# Audio.net
KiCad netlist of a schematic drawn in Altium Designer
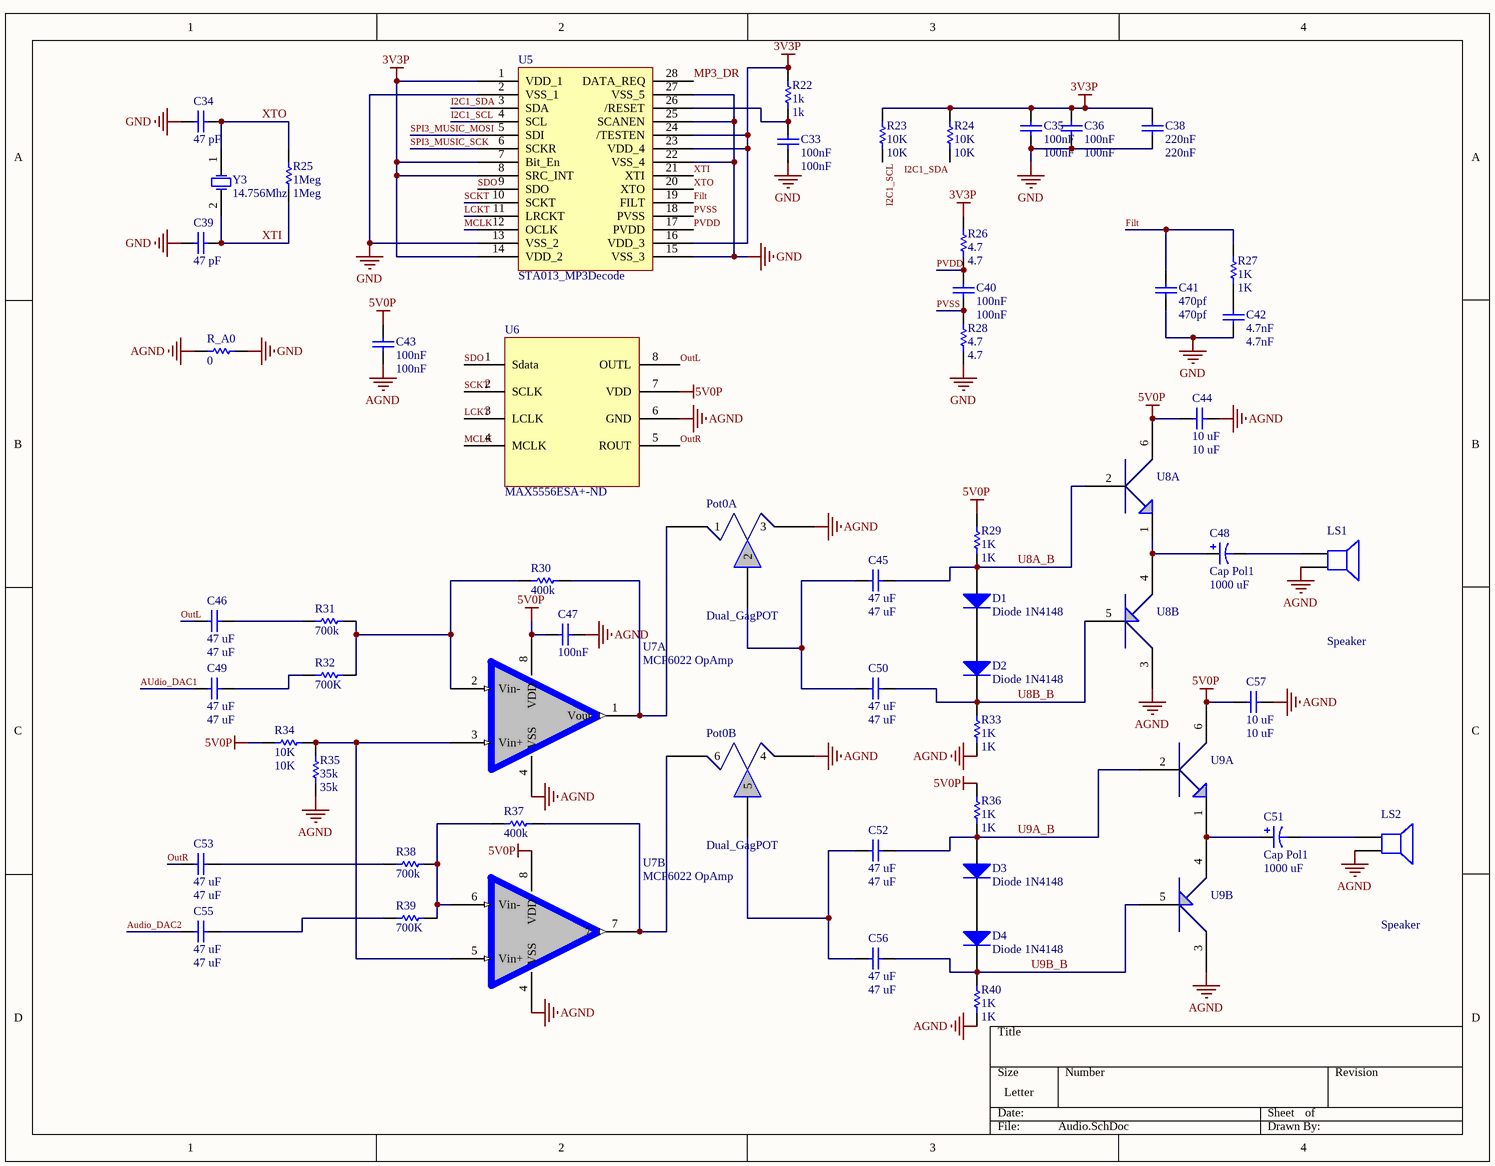
[diagram p0: Audio.SchDoc]

(export (version "E")
  (design (tool "Eeschema 10.0.6"))
  (components
    (comp (ref "C33")
      (value "100nF")
      (footprint "C0805")
      (description "Capacitor")
      (fields (field (name "ALTIUM_VALUE") "100nF") (field (name "PUBLISHER") "Altium Limited"))
      (libsource (lib "Miscellaneous Devices") (part "Cap"))
    )
    (comp (ref "C34")
      (value "47 pF")
      (footprint "C0805")
      (description "Capacitor")
      (fields (field (name "PUBLISHER") "Altium Limited"))
      (libsource (lib "Miscellaneous Devices") (part "Cap"))
    )
    (comp (ref "C35")
      (value "100nF")
      (footprint "C0805")
      (description "Capacitor")
      (fields (field (name "ALTIUM_VALUE") "100nF") (field (name "PUBLISHER") "Altium Limited"))
      (libsource (lib "Miscellaneous Devices") (part "Cap"))
    )
    (comp (ref "C36")
      (value "100nF")
      (footprint "C0805")
      (description "Capacitor")
      (fields (field (name "ALTIUM_VALUE") "100nF") (field (name "PUBLISHER") "Altium Limited"))
      (libsource (lib "Miscellaneous Devices") (part "Cap"))
    )
    (comp (ref "C38")
      (value "220nF")
      (footprint "C0805")
      (description "Capacitor")
      (fields (field (name "ALTIUM_VALUE") "220nF") (field (name "PUBLISHER") "Altium Limited"))
      (libsource (lib "Miscellaneous Devices") (part "Cap"))
    )
    (comp (ref "C39")
      (value "47 pF")
      (footprint "C0805")
      (description "Capacitor")
      (fields (field (name "PUBLISHER") "Altium Limited"))
      (libsource (lib "Miscellaneous Devices") (part "Cap"))
    )
    (comp (ref "C40")
      (value "100nF")
      (footprint "C0805")
      (description "Capacitor")
      (fields (field (name "ALTIUM_VALUE") "100nF") (field (name "PUBLISHER") "Altium Limited"))
      (libsource (lib "Miscellaneous Devices") (part "Cap"))
    )
    (comp (ref "C41")
      (value "470pf")
      (footprint "C0805")
      (description "Capacitor")
      (fields (field (name "ALTIUM_VALUE") "470pf") (field (name "PUBLISHER") "Altium Limited"))
      (libsource (lib "Miscellaneous Devices") (part "Cap"))
    )
    (comp (ref "C42")
      (value "4.7nF")
      (footprint "C0805")
      (description "Capacitor")
      (fields (field (name "ALTIUM_VALUE") "4.7nF") (field (name "PUBLISHER") "Altium Limited"))
      (libsource (lib "Miscellaneous Devices") (part "Cap"))
    )
    (comp (ref "C43")
      (value "100nF")
      (footprint "C0805")
      (description "Capacitor")
      (fields (field (name "ALTIUM_VALUE") "100nF") (field (name "PUBLISHER") "Altium Limited"))
      (libsource (lib "Miscellaneous Devices") (part "Cap"))
    )
    (comp (ref "C44")
      (value "10 uF")
      (footprint "C0805")
      (description "Capacitor")
      (fields (field (name "ALTIUM_VALUE") "10 uF") (field (name "PUBLISHER") "Altium Limited"))
      (libsource (lib "Miscellaneous Devices") (part "Cap"))
    )
    (comp (ref "C45")
      (value "47 uF")
      (footprint "C0805")
      (description "Capacitor")
      (fields (field (name "ALTIUM_VALUE") "47 uF") (field (name "PUBLISHER") "Altium Limited"))
      (libsource (lib "Miscellaneous Devices") (part "Cap"))
    )
    (comp (ref "C46")
      (value "47 uF")
      (footprint "C0805")
      (description "Capacitor")
      (fields (field (name "ALTIUM_VALUE") "47 uF") (field (name "PUBLISHER") "Altium Limited"))
      (libsource (lib "Miscellaneous Devices") (part "Cap"))
    )
    (comp (ref "C47")
      (value "100nF")
      (footprint "C0805")
      (description "Capacitor")
      (fields (field (name "PUBLISHER") "Altium Limited"))
      (libsource (lib "Miscellaneous Devices") (part "Cap"))
    )
    (comp (ref "C48")
      (value "Cap Pol1")
      (footprint "C2917")
      (description "Polarized Capacitor (Radial)")
      (fields (field (name "ALTIUM_VALUE") "1000 uF") (field (name "PUBLISHER") "Altium Limited"))
      (libsource (lib "Miscellaneous Devices") (part "Cap Pol1"))
    )
    (comp (ref "C49")
      (value "47 uF")
      (footprint "C0805")
      (description "Capacitor")
      (fields (field (name "ALTIUM_VALUE") "47 uF") (field (name "PUBLISHER") "Altium Limited"))
      (libsource (lib "Miscellaneous Devices") (part "Cap"))
    )
    (comp (ref "C50")
      (value "47 uF")
      (footprint "C0805")
      (description "Capacitor")
      (fields (field (name "ALTIUM_VALUE") "47 uF") (field (name "PUBLISHER") "Altium Limited"))
      (libsource (lib "Miscellaneous Devices") (part "Cap"))
    )
    (comp (ref "C51")
      (value "Cap Pol1")
      (footprint "C2917")
      (description "Polarized Capacitor (Radial)")
      (fields (field (name "ALTIUM_VALUE") "1000 uF") (field (name "PUBLISHER") "Altium Limited"))
      (libsource (lib "Miscellaneous Devices") (part "Cap Pol1"))
    )
    (comp (ref "C52")
      (value "47 uF")
      (footprint "C0805")
      (description "Capacitor")
      (fields (field (name "ALTIUM_VALUE") "47 uF") (field (name "PUBLISHER") "Altium Limited"))
      (libsource (lib "Miscellaneous Devices") (part "Cap"))
    )
    (comp (ref "C53")
      (value "47 uF")
      (footprint "C0805")
      (description "Capacitor")
      (fields (field (name "ALTIUM_VALUE") "47 uF") (field (name "PUBLISHER") "Altium Limited"))
      (libsource (lib "Miscellaneous Devices") (part "Cap"))
    )
    (comp (ref "C55")
      (value "47 uF")
      (footprint "C0805")
      (description "Capacitor")
      (fields (field (name "ALTIUM_VALUE") "47 uF") (field (name "PUBLISHER") "Altium Limited"))
      (libsource (lib "Miscellaneous Devices") (part "Cap"))
    )
    (comp (ref "C56")
      (value "47 uF")
      (footprint "C0805")
      (description "Capacitor")
      (fields (field (name "ALTIUM_VALUE") "47 uF") (field (name "PUBLISHER") "Altium Limited"))
      (libsource (lib "Miscellaneous Devices") (part "Cap"))
    )
    (comp (ref "C57")
      (value "10 uF")
      (footprint "C0805")
      (description "Capacitor")
      (fields (field (name "ALTIUM_VALUE") "10 uF") (field (name "PUBLISHER") "Altium Limited"))
      (libsource (lib "Miscellaneous Devices") (part "Cap"))
    )
    (comp (ref "D1")
      (value "Diode 1N4148")
      (footprint "Diode")
      (description "High Conductance Fast Diode")
      (fields (field (name "PUBLISHER") "Altium Limited"))
      (libsource (lib "Miscellaneous Devices") (part "Diode 1N4148"))
    )
    (comp (ref "D2")
      (value "Diode 1N4148")
      (footprint "Diode")
      (description "High Conductance Fast Diode")
      (fields (field (name "PUBLISHER") "Altium Limited"))
      (libsource (lib "Miscellaneous Devices") (part "Diode 1N4148"))
    )
    (comp (ref "D3")
      (value "Diode 1N4148")
      (footprint "Diode")
      (description "High Conductance Fast Diode")
      (fields (field (name "PUBLISHER") "Altium Limited"))
      (libsource (lib "Miscellaneous Devices") (part "Diode 1N4148"))
    )
    (comp (ref "D4")
      (value "Diode 1N4148")
      (footprint "Diode")
      (description "High Conductance Fast Diode")
      (fields (field (name "PUBLISHER") "Altium Limited"))
      (libsource (lib "Miscellaneous Devices") (part "Diode 1N4148"))
    )
    (comp (ref "LS1")
      (value "Speaker")
      (footprint "PIN2")
      (description "Loudspeaker")
      (fields (field (name "PUBLISHER") "Altium Limited"))
      (libsource (lib "Miscellaneous Devices") (part "Speaker"))
    )
    (comp (ref "LS2")
      (value "Speaker")
      (footprint "PIN2")
      (description "Loudspeaker")
      (fields (field (name "PUBLISHER") "Altium Limited"))
      (libsource (lib "Miscellaneous Devices") (part "Speaker"))
    )
    (comp (ref "Pot0")
      (value "Dual_GagPOT")
      (footprint "DGPOT")
      (libsource (lib "GameMan_SchLib") (part "Dual_GagPOT"))
    )
    (comp (ref "R22")
      (value "1k")
      (footprint "6-0805_M")
      (description "Resistor")
      (fields (field (name "ALTIUM_VALUE") "1k") (field (name "PUBLISHER") "Altium Limited"))
      (libsource (lib "Miscellaneous Devices") (part "Res1"))
    )
    (comp (ref "R23")
      (value "10K")
      (footprint "6-0805_M")
      (description "Resistor")
      (fields (field (name "ALTIUM_VALUE") "10K") (field (name "PUBLISHER") "Altium Limited"))
      (libsource (lib "Miscellaneous Devices") (part "Res1"))
    )
    (comp (ref "R24")
      (value "10K")
      (footprint "6-0805_M")
      (description "Resistor")
      (fields (field (name "ALTIUM_VALUE") "10K") (field (name "PUBLISHER") "Altium Limited"))
      (libsource (lib "Miscellaneous Devices") (part "Res1"))
    )
    (comp (ref "R25")
      (value "1Meg")
      (footprint "6-0805_M")
      (description "Resistor")
      (fields (field (name "ALTIUM_VALUE") "1Meg") (field (name "PUBLISHER") "Altium Limited"))
      (libsource (lib "Miscellaneous Devices") (part "Res1"))
    )
    (comp (ref "R26")
      (value "4.7")
      (footprint "6-0805_M")
      (description "Resistor")
      (fields (field (name "ALTIUM_VALUE") "4.7") (field (name "PUBLISHER") "Altium Limited"))
      (libsource (lib "Miscellaneous Devices") (part "Res1"))
    )
    (comp (ref "R27")
      (value "1K")
      (footprint "6-0805_M")
      (description "Resistor")
      (fields (field (name "ALTIUM_VALUE") "1K") (field (name "PUBLISHER") "Altium Limited"))
      (libsource (lib "Miscellaneous Devices") (part "Res1"))
    )
    (comp (ref "R28")
      (value "4.7")
      (footprint "6-0805_M")
      (description "Resistor")
      (fields (field (name "ALTIUM_VALUE") "4.7") (field (name "PUBLISHER") "Altium Limited"))
      (libsource (lib "Miscellaneous Devices") (part "Res1"))
    )
    (comp (ref "R29")
      (value "1K")
      (footprint "6-0805_M")
      (description "Resistor")
      (fields (field (name "ALTIUM_VALUE") "1K") (field (name "PUBLISHER") "Altium Limited"))
      (libsource (lib "Miscellaneous Devices") (part "Res1"))
    )
    (comp (ref "R30")
      (value "400k")
      (footprint "6-0805_M")
      (description "Resistor")
      (fields (field (name "PUBLISHER") "Altium Limited"))
      (libsource (lib "Miscellaneous Devices") (part "Res1"))
    )
    (comp (ref "R31")
      (value "700k")
      (footprint "6-0805_M")
      (description "Resistor")
      (fields (field (name "PUBLISHER") "Altium Limited"))
      (libsource (lib "Miscellaneous Devices") (part "Res1"))
    )
    (comp (ref "R32")
      (value "700K")
      (footprint "6-0805_M")
      (description "Resistor")
      (fields (field (name "PUBLISHER") "Altium Limited"))
      (libsource (lib "Miscellaneous Devices") (part "Res1"))
    )
    (comp (ref "R33")
      (value "1K")
      (footprint "6-0805_M")
      (description "Resistor")
      (fields (field (name "ALTIUM_VALUE") "1K") (field (name "PUBLISHER") "Altium Limited"))
      (libsource (lib "Miscellaneous Devices") (part "Res1"))
    )
    (comp (ref "R34")
      (value "10K")
      (footprint "6-0805_M")
      (description "Resistor")
      (fields (field (name "ALTIUM_VALUE") "10K") (field (name "PUBLISHER") "Altium Limited"))
      (libsource (lib "Miscellaneous Devices") (part "Res1"))
    )
    (comp (ref "R35")
      (value "35k")
      (footprint "6-0805_M")
      (description "Resistor")
      (fields (field (name "ALTIUM_VALUE") "35k") (field (name "PUBLISHER") "Altium Limited"))
      (libsource (lib "Miscellaneous Devices") (part "Res1"))
    )
    (comp (ref "R36")
      (value "1K")
      (footprint "6-0805_M")
      (description "Resistor")
      (fields (field (name "ALTIUM_VALUE") "1K") (field (name "PUBLISHER") "Altium Limited"))
      (libsource (lib "Miscellaneous Devices") (part "Res1"))
    )
    (comp (ref "R37")
      (value "400k")
      (footprint "6-0805_M")
      (description "Resistor")
      (fields (field (name "PUBLISHER") "Altium Limited"))
      (libsource (lib "Miscellaneous Devices") (part "Res1"))
    )
    (comp (ref "R38")
      (value "700k")
      (footprint "6-0805_M")
      (description "Resistor")
      (fields (field (name "PUBLISHER") "Altium Limited"))
      (libsource (lib "Miscellaneous Devices") (part "Res1"))
    )
    (comp (ref "R39")
      (value "700K")
      (footprint "6-0805_M")
      (description "Resistor")
      (fields (field (name "PUBLISHER") "Altium Limited"))
      (libsource (lib "Miscellaneous Devices") (part "Res1"))
    )
    (comp (ref "R40")
      (value "1K")
      (footprint "6-0805_M")
      (description "Resistor")
      (fields (field (name "ALTIUM_VALUE") "1K") (field (name "PUBLISHER") "Altium Limited"))
      (libsource (lib "Miscellaneous Devices") (part "Res1"))
    )
    (comp (ref "R_A0")
      (value "0")
      (footprint "6-0805_M")
      (description "Resistor")
      (fields (field (name "PUBLISHER") "Altium Limited"))
      (libsource (lib "Miscellaneous Devices") (part "Res1"))
    )
    (comp (ref "U5")
      (value "STA013_MP3Decode")
      (footprint "SOP28")
      (libsource (lib "Parts") (part "STA013_MP3Decode"))
    )
    (comp (ref "U6")
      (value "MAX5556ESA+-ND")
      (footprint "SOIC8_DAC")
      (libsource (lib "Parts") (part "MAX5556ESA+-ND"))
    )
    (comp (ref "U7")
      (value "MCP6022 OpAmp")
      (footprint "SOP8_Opamp")
      (libsource (lib "GameMan") (part "MCP6022 OpAmp"))
    )
    (comp (ref "U8") (value "BJT") (footprint "BJT_SOT6") (libsource (lib "GameMan") (part "BJT")))
    (comp (ref "U9") (value "BJT") (footprint "BJT_SOT6") (libsource (lib "GameMan") (part "BJT")))
    (comp (ref "Y3")
      (value "14.756Mhz")
      (footprint "HC-49U")
      (description "Crystal Oscillator")
      (fields (field (name "PUBLISHER") "Altium Limited"))
      (libsource (lib "Miscellaneous Devices") (part "XTAL"))
    )
  )
  (nets
    (net (code "1") (name "/AUdio_DAC1") (class "Default")
      (node (ref "C49") (pin "1") (pinfunction "1_1") (pintype "passive"))
    )
    (net (code "2") (name "/Audio_DAC2") (class "Default")
      (node (ref "C55") (pin "1") (pinfunction "1_1") (pintype "passive"))
    )
    (net (code "3") (name "/Filt") (class "Default")
      (node (ref "C41") (pin "2") (pinfunction "2_2") (pintype "passive"))
      (node (ref "R27") (pin "1") (pinfunction "1_1") (pintype "passive"))
      (node (ref "U5") (pin "19") (pinfunction "FILT_19") (pintype "passive"))
    )
    (net (code "4") (name "/I2C1_SCL") (class "Default")
      (node (ref "R23") (pin "1") (pinfunction "1_1") (pintype "passive"))
      (node (ref "U5") (pin "4") (pinfunction "SCL_4") (pintype "passive"))
    )
    (net (code "5") (name "/I2C1_SDA") (class "Default")
      (node (ref "R24") (pin "1") (pinfunction "1_1") (pintype "passive"))
      (node (ref "U5") (pin "3") (pinfunction "SDA_3") (pintype "passive"))
    )
    (net (code "6") (name "/LCKT") (class "Default")
      (node (ref "U5") (pin "11") (pinfunction "LRCKT_11") (pintype "passive"))
      (node (ref "U6") (pin "3") (pinfunction "LCLK_3") (pintype "passive"))
    )
    (net (code "7") (name "/MCLK") (class "Default")
      (node (ref "U5") (pin "12") (pinfunction "OCLK_12") (pintype "passive"))
      (node (ref "U6") (pin "4") (pinfunction "MCLK_4") (pintype "passive"))
    )
    (net (code "8") (name "/MP3_DR") (class "Default")
      (node (ref "U5") (pin "28") (pinfunction "DATA_REQ_28") (pintype "passive"))
    )
    (net (code "9") (name "/OutL") (class "Default")
      (node (ref "C46") (pin "1") (pinfunction "1_1") (pintype "passive"))
      (node (ref "U6") (pin "8") (pinfunction "OUTL_8") (pintype "passive"))
    )
    (net (code "10") (name "/OutR") (class "Default")
      (node (ref "C53") (pin "1") (pinfunction "1_1") (pintype "passive"))
      (node (ref "U6") (pin "5") (pinfunction "ROUT_5") (pintype "passive"))
    )
    (net (code "11") (name "/PVDD") (class "Default")
      (node (ref "C40") (pin "2") (pinfunction "2_2") (pintype "passive"))
      (node (ref "R26") (pin "2") (pinfunction "2_2") (pintype "passive"))
      (node (ref "U5") (pin "17") (pinfunction "PVDD_17") (pintype "passive"))
    )
    (net (code "12") (name "/PVSS") (class "Default")
      (node (ref "C40") (pin "1") (pinfunction "1_1") (pintype "passive"))
      (node (ref "R28") (pin "1") (pinfunction "1_1") (pintype "passive"))
      (node (ref "U5") (pin "18") (pinfunction "PVSS_18") (pintype "passive"))
    )
    (net (code "13") (name "/SCKT") (class "Default")
      (node (ref "U5") (pin "10") (pinfunction "SCKT_10") (pintype "passive"))
      (node (ref "U6") (pin "2") (pinfunction "SCLK_2") (pintype "passive"))
    )
    (net (code "14") (name "/SDO") (class "Default")
      (node (ref "U5") (pin "9") (pinfunction "SDO_9") (pintype "passive"))
      (node (ref "U6") (pin "1") (pinfunction "Sdata_1") (pintype "passive"))
    )
    (net (code "15") (name "/SPI3_MUSIC_MOSI") (class "Default")
      (node (ref "U5") (pin "5") (pinfunction "SDI_5") (pintype "passive"))
    )
    (net (code "16") (name "/SPI3_MUSIC_SCK") (class "Default")
      (node (ref "U5") (pin "6") (pinfunction "SCKR_6") (pintype "passive"))
    )
    (net (code "17") (name "/U8A_B") (class "Default")
      (node (ref "C45") (pin "2") (pinfunction "2_2") (pintype "passive"))
      (node (ref "D1") (pin "A") (pinfunction "A_A") (pintype "passive"))
      (node (ref "R29") (pin "2") (pinfunction "2_2") (pintype "passive"))
      (node (ref "U8") (pin "2") (pinfunction "Base_2") (pintype "power_in"))
    )
    (net (code "18") (name "/U8B_B") (class "Default")
      (node (ref "C50") (pin "2") (pinfunction "2_2") (pintype "passive"))
      (node (ref "D2") (pin "K") (pinfunction "K_K") (pintype "passive"))
      (node (ref "R33") (pin "1") (pinfunction "1_1") (pintype "passive"))
      (node (ref "U8") (pin "5") (pinfunction "Base_5") (pintype "power_in"))
    )
    (net (code "19") (name "/U9A_B") (class "Default")
      (node (ref "C52") (pin "2") (pinfunction "2_2") (pintype "passive"))
      (node (ref "D3") (pin "A") (pinfunction "A_A") (pintype "passive"))
      (node (ref "R36") (pin "2") (pinfunction "2_2") (pintype "passive"))
      (node (ref "U9") (pin "2") (pinfunction "Base_2") (pintype "power_in"))
    )
    (net (code "20") (name "/U9B_B") (class "Default")
      (node (ref "C56") (pin "2") (pinfunction "2_2") (pintype "passive"))
      (node (ref "D4") (pin "K") (pinfunction "K_K") (pintype "passive"))
      (node (ref "R40") (pin "1") (pinfunction "1_1") (pintype "passive"))
      (node (ref "U9") (pin "5") (pinfunction "Base_5") (pintype "power_in"))
    )
    (net (code "21") (name "/XTI") (class "Default")
      (node (ref "C39") (pin "2") (pinfunction "2_2") (pintype "passive"))
      (node (ref "R25") (pin "1") (pinfunction "1_1") (pintype "passive"))
      (node (ref "U5") (pin "21") (pinfunction "XTI_21") (pintype "passive"))
      (node (ref "Y3") (pin "2") (pinfunction "OSC2_2") (pintype "passive"))
    )
    (net (code "22") (name "/XTO") (class "Default")
      (node (ref "C34") (pin "2") (pinfunction "2_2") (pintype "passive"))
      (node (ref "R25") (pin "2") (pinfunction "2_2") (pintype "passive"))
      (node (ref "U5") (pin "20") (pinfunction "XTO_20") (pintype "passive"))
      (node (ref "Y3") (pin "1") (pinfunction "OSC1_1") (pintype "passive"))
    )
    (net (code "23") (name "3V3P") (class "Default")
      (node (ref "C35") (pin "2") (pinfunction "2_2") (pintype "passive"))
      (node (ref "C36") (pin "2") (pinfunction "2_2") (pintype "passive"))
      (node (ref "C38") (pin "2") (pinfunction "2_2") (pintype "passive"))
      (node (ref "R22") (pin "2") (pinfunction "2_2") (pintype "passive"))
      (node (ref "R23") (pin "2") (pinfunction "2_2") (pintype "passive"))
      (node (ref "R24") (pin "2") (pinfunction "2_2") (pintype "passive"))
      (node (ref "R26") (pin "1") (pinfunction "1_1") (pintype "passive"))
      (node (ref "U5") (pin "1") (pinfunction "VDD_1_1") (pintype "passive"))
      (node (ref "U5") (pin "14") (pinfunction "VDD_2_14") (pintype "passive"))
      (node (ref "U5") (pin "16") (pinfunction "VDD_3_16") (pintype "passive"))
      (node (ref "U5") (pin "23") (pinfunction "VDD_4_23") (pintype "passive"))
      (node (ref "U5") (pin "24") (pinfunction "/TESTEN_24") (pintype "passive"))
      (node (ref "U5") (pin "7") (pinfunction "Bit_En_7") (pintype "passive"))
      (node (ref "U5") (pin "8") (pinfunction "SRC_INT_8") (pintype "passive"))
    )
    (net (code "24") (name "5V0P") (class "Default")
      (node (ref "C43") (pin "2") (pinfunction "2_2") (pintype "passive"))
      (node (ref "C44") (pin "2") (pinfunction "2_2") (pintype "passive"))
      (node (ref "C47") (pin "1") (pinfunction "1_1") (pintype "passive"))
      (node (ref "C57") (pin "2") (pinfunction "2_2") (pintype "passive"))
      (node (ref "R29") (pin "1") (pinfunction "1_1") (pintype "passive"))
      (node (ref "R34") (pin "1") (pinfunction "1_1") (pintype "passive"))
      (node (ref "R36") (pin "1") (pinfunction "1_1") (pintype "passive"))
      (node (ref "U6") (pin "7") (pinfunction "VDD_7") (pintype "passive"))
      (node (ref "U7") (pin "8") (pinfunction "VDD_8") (pintype "power_in"))
      (node (ref "U8") (pin "6") (pinfunction "Collector_6") (pintype "power_in"))
      (node (ref "U9") (pin "6") (pinfunction "Collector_6") (pintype "power_in"))
    )
    (net (code "25") (name "AGND") (class "Default")
      (node (ref "C43") (pin "1") (pinfunction "1_1") (pintype "passive"))
      (node (ref "C44") (pin "1") (pinfunction "1_1") (pintype "passive"))
      (node (ref "C47") (pin "2") (pinfunction "2_2") (pintype "passive"))
      (node (ref "C57") (pin "1") (pinfunction "1_1") (pintype "passive"))
      (node (ref "LS1") (pin "2") (pinfunction "2_2") (pintype "passive"))
      (node (ref "LS2") (pin "2") (pinfunction "2_2") (pintype "passive"))
      (node (ref "Pot0") (pin "3") (pinfunction "3_3") (pintype "passive"))
      (node (ref "Pot0") (pin "4") (pinfunction "4_4") (pintype "passive"))
      (node (ref "R33") (pin "2") (pinfunction "2_2") (pintype "passive"))
      (node (ref "R35") (pin "1") (pinfunction "1_1") (pintype "passive"))
      (node (ref "R40") (pin "2") (pinfunction "2_2") (pintype "passive"))
      (node (ref "R_A0") (pin "1") (pinfunction "1_1") (pintype "passive"))
      (node (ref "U6") (pin "6") (pinfunction "GND_6") (pintype "passive"))
      (node (ref "U7") (pin "4") (pinfunction "VSS_4") (pintype "power_in"))
      (node (ref "U8") (pin "3") (pinfunction "Collector_3") (pintype "power_in"))
      (node (ref "U9") (pin "3") (pinfunction "Collector_3") (pintype "power_in"))
    )
    (net (code "26") (name "GND") (class "Default")
      (node (ref "C33") (pin "2") (pinfunction "2_2") (pintype "passive"))
      (node (ref "C34") (pin "1") (pinfunction "1_1") (pintype "passive"))
      (node (ref "C35") (pin "1") (pinfunction "1_1") (pintype "passive"))
      (node (ref "C36") (pin "1") (pinfunction "1_1") (pintype "passive"))
      (node (ref "C38") (pin "1") (pinfunction "1_1") (pintype "passive"))
      (node (ref "C39") (pin "1") (pinfunction "1_1") (pintype "passive"))
      (node (ref "C41") (pin "1") (pinfunction "1_1") (pintype "passive"))
      (node (ref "C42") (pin "1") (pinfunction "1_1") (pintype "passive"))
      (node (ref "R28") (pin "2") (pinfunction "2_2") (pintype "passive"))
      (node (ref "R_A0") (pin "2") (pinfunction "2_2") (pintype "passive"))
      (node (ref "U5") (pin "13") (pinfunction "VSS_2_13") (pintype "passive"))
      (node (ref "U5") (pin "15") (pinfunction "VSS_3_15") (pintype "passive"))
      (node (ref "U5") (pin "2") (pinfunction "VSS_1_2") (pintype "passive"))
      (node (ref "U5") (pin "22") (pinfunction "VSS_4_22") (pintype "passive"))
      (node (ref "U5") (pin "25") (pinfunction "SCANEN_25") (pintype "passive"))
      (node (ref "U5") (pin "27") (pinfunction "VSS_5_27") (pintype "passive"))
    )
    (net (code "27") (name "Net-(C42-Pad2)") (class "Default")
      (node (ref "C42") (pin "2") (pinfunction "2_2") (pintype "passive"))
      (node (ref "R27") (pin "2") (pinfunction "2_2") (pintype "passive"))
    )
    (net (code "28") (name "Net-(C45-Pad1)") (class "Default")
      (node (ref "C45") (pin "1") (pinfunction "1_1") (pintype "passive"))
      (node (ref "C50") (pin "1") (pinfunction "1_1") (pintype "passive"))
      (node (ref "Pot0") (pin "2") (pinfunction "2_2") (pintype "passive"))
    )
    (net (code "29") (name "Net-(C46-Pad2)") (class "Default")
      (node (ref "C46") (pin "2") (pinfunction "2_2") (pintype "passive"))
      (node (ref "R31") (pin "1") (pinfunction "1_1") (pintype "passive"))
    )
    (net (code "30") (name "Net-(C48-Pad2)") (class "Default")
      (node (ref "C48") (pin "2") (pinfunction "2_2") (pintype "passive"))
      (node (ref "LS1") (pin "1") (pinfunction "1_1") (pintype "passive"))
    )
    (net (code "31") (name "Net-(C49-Pad2)") (class "Default")
      (node (ref "C49") (pin "2") (pinfunction "2_2") (pintype "passive"))
      (node (ref "R32") (pin "1") (pinfunction "1_1") (pintype "passive"))
    )
    (net (code "32") (name "Net-(C51-Pad2)") (class "Default")
      (node (ref "C51") (pin "2") (pinfunction "2_2") (pintype "passive"))
      (node (ref "LS2") (pin "1") (pinfunction "1_1") (pintype "passive"))
    )
    (net (code "33") (name "Net-(C52-Pad1)") (class "Default")
      (node (ref "C52") (pin "1") (pinfunction "1_1") (pintype "passive"))
      (node (ref "C56") (pin "1") (pinfunction "1_1") (pintype "passive"))
      (node (ref "Pot0") (pin "5") (pinfunction "5_5") (pintype "passive"))
    )
    (net (code "34") (name "Net-(C53-Pad2)") (class "Default")
      (node (ref "C53") (pin "2") (pinfunction "2_2") (pintype "passive"))
      (node (ref "R38") (pin "1") (pinfunction "1_1") (pintype "passive"))
    )
    (net (code "35") (name "Net-(C55-Pad2)") (class "Default")
      (node (ref "C55") (pin "2") (pinfunction "2_2") (pintype "passive"))
      (node (ref "R39") (pin "1") (pinfunction "1_1") (pintype "passive"))
    )
    (net (code "36") (name "Net-(D1-PadK)") (class "Default")
      (node (ref "D1") (pin "K") (pinfunction "K_K") (pintype "passive"))
      (node (ref "D2") (pin "A") (pinfunction "A_A") (pintype "passive"))
    )
    (net (code "37") (name "Net-(D3-PadK)") (class "Default")
      (node (ref "D3") (pin "K") (pinfunction "K_K") (pintype "passive"))
      (node (ref "D4") (pin "A") (pinfunction "A_A") (pintype "passive"))
    )
    (net (code "38") (name "Net-(Pot0-Pad6)") (class "Default")
      (node (ref "Pot0") (pin "6") (pinfunction "6_6") (pintype "passive"))
      (node (ref "R37") (pin "2") (pinfunction "2_2") (pintype "passive"))
      (node (ref "U7") (pin "7") (pinfunction "7_7") (pintype "output"))
    )
    (net (code "39") (name "Net-(U5-{slash}RESET)") (class "Default")
      (node (ref "C33") (pin "1") (pinfunction "1_1") (pintype "passive"))
      (node (ref "R22") (pin "1") (pinfunction "1_1") (pintype "passive"))
      (node (ref "U5") (pin "26") (pinfunction "/RESET_26") (pintype "passive"))
    )
    (net (code "40") (name "Net-(U7A-Vin+)") (class "Default")
      (node (ref "R34") (pin "2") (pinfunction "2_2") (pintype "passive"))
      (node (ref "R35") (pin "2") (pinfunction "2_2") (pintype "passive"))
      (node (ref "U7") (pin "3") (pinfunction "Vin+_3") (pintype "input"))
      (node (ref "U7") (pin "5") (pinfunction "Vin+_5") (pintype "input"))
    )
    (net (code "41") (name "Net-(U7A-Vin-)") (class "Default")
      (node (ref "R30") (pin "1") (pinfunction "1_1") (pintype "passive"))
      (node (ref "R31") (pin "2") (pinfunction "2_2") (pintype "passive"))
      (node (ref "R32") (pin "2") (pinfunction "2_2") (pintype "passive"))
      (node (ref "U7") (pin "2") (pinfunction "Vin-_2") (pintype "input"))
    )
    (net (code "42") (name "Net-(U7A-Vout)") (class "Default")
      (node (ref "Pot0") (pin "1") (pinfunction "1_1") (pintype "passive"))
      (node (ref "R30") (pin "2") (pinfunction "2_2") (pintype "passive"))
      (node (ref "U7") (pin "1") (pinfunction "Vout_1") (pintype "output"))
    )
    (net (code "43") (name "Net-(U7B-Vin-)") (class "Default")
      (node (ref "R37") (pin "1") (pinfunction "1_1") (pintype "passive"))
      (node (ref "R38") (pin "2") (pinfunction "2_2") (pintype "passive"))
      (node (ref "R39") (pin "2") (pinfunction "2_2") (pintype "passive"))
      (node (ref "U7") (pin "6") (pinfunction "Vin-_6") (pintype "input"))
    )
    (net (code "44") (name "Net-(U8A-Emitter)") (class "Default")
      (node (ref "C48") (pin "1") (pinfunction "1_1") (pintype "passive"))
      (node (ref "U8") (pin "1") (pinfunction "Emitter_1") (pintype "power_in"))
      (node (ref "U8") (pin "4") (pinfunction "Emitter_4") (pintype "power_in"))
    )
    (net (code "45") (name "Net-(U9A-Emitter)") (class "Default")
      (node (ref "C51") (pin "1") (pinfunction "1_1") (pintype "passive"))
      (node (ref "U9") (pin "1") (pinfunction "Emitter_1") (pintype "power_in"))
      (node (ref "U9") (pin "4") (pinfunction "Emitter_4") (pintype "power_in"))
    )
  )
)
